# Pcbdesign_power_module.net
KiCad netlist of a schematic drawn in EAGLE
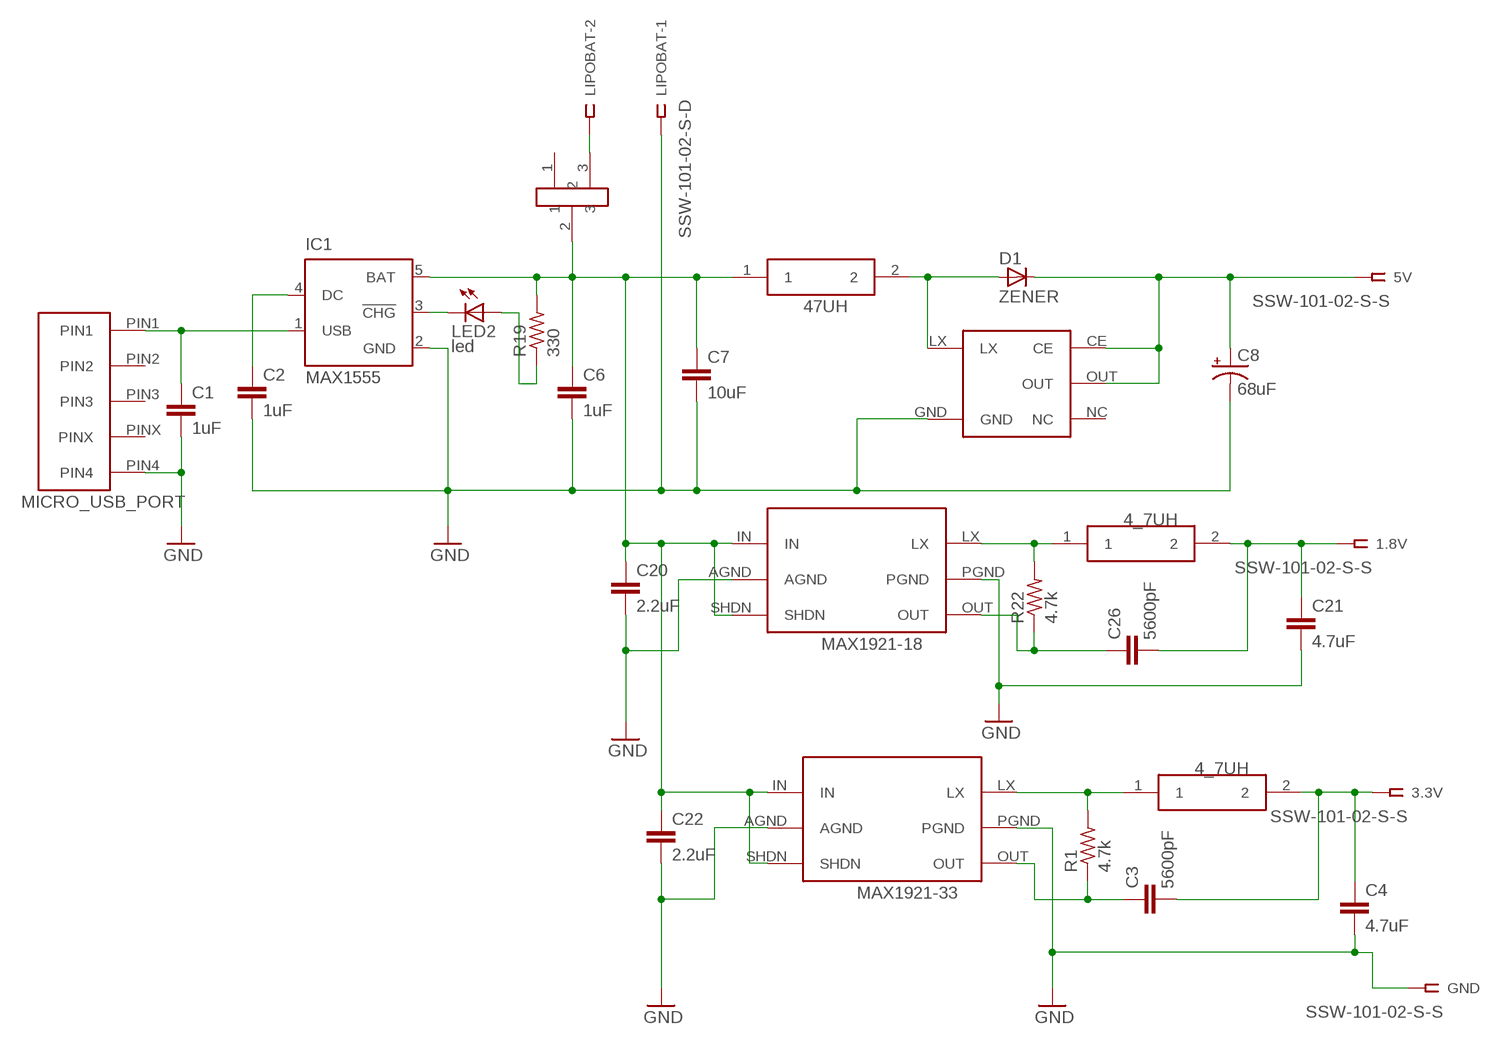
[diagram p0: schematic, sheet 1]

(export (version "E")
  (design (tool "Eeschema 10.0.6"))
  (components
    (comp (ref "1.8V")
      (value "SSW-101-02-S-S")
      (footprint "eagle-import:SSW-101-02-S-S")
      (libsource (lib "eagle-import") (part "SSW-101-02-S-S"))
    )
    (comp (ref "3.3V")
      (value "SSW-101-02-S-S")
      (footprint "eagle-import:SSW-101-02-S-S")
      (libsource (lib "eagle-import") (part "SSW-101-02-S-S"))
    )
    (comp (ref "5V")
      (value "SSW-101-02-S-S")
      (footprint "eagle-import:SSW-101-02-S-S")
      (libsource (lib "eagle-import") (part "SSW-101-02-S-S"))
    )
    (comp (ref "10UH")
      (value "SUMIDA_10U")
      (footprint "eagle-import:SUMIDA_10U")
      (libsource (lib "eagle-import") (part "SUMIDA_10U"))
    )
    (comp (ref "C1")
      (value "1uF")
      (footprint "eagle-import:C0805K")
      (libsource (lib "eagle-import") (part "C-EUC0805K"))
    )
    (comp (ref "C2")
      (value "1uF")
      (footprint "eagle-import:C0805K")
      (libsource (lib "eagle-import") (part "C-EUC0805K"))
    )
    (comp (ref "C3")
      (value "5600pF")
      (footprint "eagle-import:C0805K")
      (libsource (lib "eagle-import") (part "C-EUC0805K"))
    )
    (comp (ref "C4")
      (value "4.7uF")
      (footprint "eagle-import:C0805K")
      (libsource (lib "eagle-import") (part "C-EUC0805K"))
    )
    (comp (ref "C6")
      (value "1uF")
      (footprint "eagle-import:C0805K")
      (libsource (lib "eagle-import") (part "C-EUC0805K"))
    )
    (comp (ref "C7")
      (value "10uF")
      (footprint "eagle-import:C0805K")
      (libsource (lib "eagle-import") (part "C-EUC0805K"))
    )
    (comp (ref "C8")
      (value "68uF")
      (footprint "eagle-import:C_6032-28R")
      (libsource (lib "eagle-import") (part "CPOL-USC/6032-28R"))
    )
    (comp (ref "C20")
      (value "2.2uF")
      (footprint "eagle-import:C0805K")
      (libsource (lib "eagle-import") (part "C-EUC0805K"))
    )
    (comp (ref "C21")
      (value "4.7uF")
      (footprint "eagle-import:C0805K")
      (libsource (lib "eagle-import") (part "C-EUC0805K"))
    )
    (comp (ref "C22")
      (value "2.2uF")
      (footprint "eagle-import:C0805K")
      (libsource (lib "eagle-import") (part "C-EUC0805K"))
    )
    (comp (ref "C26")
      (value "5600pF")
      (footprint "eagle-import:C0805K")
      (libsource (lib "eagle-import") (part "C-EUC0805K"))
    )
    (comp (ref "D1")
      (value "ZENER")
      (footprint "eagle-import:SOD123")
      (libsource (lib "eagle-import") (part "D-SOD123"))
    )
    (comp (ref "GND")
      (value "SSW-101-02-S-S")
      (footprint "eagle-import:SSW-101-02-S-S")
      (libsource (lib "eagle-import") (part "SSW-101-02-S-S"))
    )
    (comp (ref "IC1")
      (value "MAX1555")
      (footprint "eagle-import:SOT23-5L")
      (fields (field (name "MF") "MAXIM") (field (name "MPN") "MAX1555EZK+T"))
      (libsource (lib "eagle-import") (part "MAX1555"))
    )
    (comp (ref "LED2")
      (value "led")
      (footprint "eagle-import:CHIPLED_0603")
      (libsource (lib "eagle-import") (part "LEDCHIPLED_0603"))
    )
    (comp (ref "LIPOBAT")
      (value "SSW-101-02-S-D")
      (footprint "eagle-import:SSW-101-02-S-D")
      (libsource (lib "eagle-import") (part "SSW-101-02-S-D"))
    )
    (comp (ref "MAX1920")
      (value "MAX1921")
      (footprint "eagle-import:MAX1921")
      (libsource (lib "eagle-import") (part "MAX1921"))
    )
    (comp (ref "MAX1921-18")
      (value "MAX1921")
      (footprint "eagle-import:MAX1921")
      (libsource (lib "eagle-import") (part "MAX1921"))
    )
    (comp (ref "MICRO_USB")
      (value "10118192")
      (footprint "eagle-import:10118192")
      (libsource (lib "eagle-import") (part "10118192"))
    )
    (comp (ref "R1")
      (value "4.7k")
      (footprint "eagle-import:R0805")
      (libsource (lib "eagle-import") (part "R-US_R0805"))
    )
    (comp (ref "R19")
      (value "330")
      (footprint "eagle-import:R0805")
      (libsource (lib "eagle-import") (part "R-US_R0805"))
    )
    (comp (ref "R22")
      (value "4.7k")
      (footprint "eagle-import:R0805")
      (libsource (lib "eagle-import") (part "R-US_R0805"))
    )
    (comp (ref "U$1")
      (value "SUMIDA_4.7U")
      (footprint "eagle-import:SUMIDA_4.7U")
      (libsource (lib "eagle-import") (part "SUMIDA_4.7U"))
    )
    (comp (ref "U$2")
      (value "SUMIDA_4.7U")
      (footprint "eagle-import:SUMIDA_4.7U")
      (libsource (lib "eagle-import") (part "SUMIDA_4.7U"))
    )
    (comp (ref "U$3")
      (value "NPC1402")
      (footprint "eagle-import:NPC1402")
      (libsource (lib "eagle-import") (part "NPC1402"))
    )
    (comp (ref "U$4")
      (value "SWITCH111")
      (footprint "eagle-import:SWITCH111")
      (libsource (lib "eagle-import") (part "SWITCH111"))
    )
  )
  (nets
    (net (code "1") (name "GND") (class "Default")
      (node (ref "C1") (pin "2") (pinfunction "2_2") (pintype "passive"))
      (node (ref "C2") (pin "2") (pinfunction "2_2") (pintype "passive"))
      (node (ref "C20") (pin "2") (pinfunction "2_2") (pintype "passive"))
      (node (ref "C21") (pin "2") (pinfunction "2_2") (pintype "passive"))
      (node (ref "C22") (pin "2") (pinfunction "2_2") (pintype "passive"))
      (node (ref "C4") (pin "2") (pinfunction "2_2") (pintype "passive"))
      (node (ref "C6") (pin "2") (pinfunction "2_2") (pintype "passive"))
      (node (ref "C7") (pin "2") (pinfunction "2_2") (pintype "passive"))
      (node (ref "C8") (pin "-") (pinfunction "-_-") (pintype "passive"))
      (node (ref "GND") (pin "1") (pinfunction "1_1") (pintype "passive"))
      (node (ref "IC1") (pin "2") (pinfunction "GND_2") (pintype "power_in"))
      (node (ref "LIPOBAT") (pin "1") (pinfunction "1_1") (pintype "passive"))
      (node (ref "MAX1920") (pin "AGND") (pinfunction "AGND_AGND") (pintype "bidirectional"))
      (node (ref "MAX1920") (pin "PGND") (pinfunction "PGND_PGND") (pintype "bidirectional"))
      (node (ref "MAX1921-18") (pin "AGND") (pinfunction "AGND_AGND") (pintype "bidirectional"))
      (node (ref "MAX1921-18") (pin "PGND") (pinfunction "PGND_PGND") (pintype "bidirectional"))
      (node (ref "MICRO_USB") (pin "PIN4") (pinfunction "PIN4_PIN4") (pintype "bidirectional"))
      (node (ref "U$3") (pin "GND") (pinfunction "GND_GND") (pintype "bidirectional"))
    )
    (net (code "2") (name "Net-(1.8V-Pad1)") (class "Default")
      (node (ref "1.8V") (pin "1") (pinfunction "1_1") (pintype "passive"))
      (node (ref "C21") (pin "1") (pinfunction "1_1") (pintype "passive"))
      (node (ref "C26") (pin "2") (pinfunction "2_2") (pintype "passive"))
      (node (ref "U$1") (pin "2") (pinfunction "2_2") (pintype "bidirectional"))
    )
    (net (code "3") (name "Net-(3.3V-Pad1)") (class "Default")
      (node (ref "3.3V") (pin "1") (pinfunction "1_1") (pintype "passive"))
      (node (ref "C3") (pin "2") (pinfunction "2_2") (pintype "passive"))
      (node (ref "C4") (pin "1") (pinfunction "1_1") (pintype "passive"))
      (node (ref "U$2") (pin "2") (pinfunction "2_2") (pintype "bidirectional"))
    )
    (net (code "4") (name "Net-(C3-Pad1)") (class "Default")
      (node (ref "C3") (pin "1") (pinfunction "1_1") (pintype "passive"))
      (node (ref "MAX1920") (pin "OUT") (pinfunction "OUT_OUT") (pintype "bidirectional"))
      (node (ref "R1") (pin "1") (pinfunction "1_1") (pintype "passive"))
    )
    (net (code "5") (name "Net-(C26-Pad1)") (class "Default")
      (node (ref "C26") (pin "1") (pinfunction "1_1") (pintype "passive"))
      (node (ref "MAX1921-18") (pin "OUT") (pinfunction "OUT_OUT") (pintype "bidirectional"))
      (node (ref "R22") (pin "1") (pinfunction "1_1") (pintype "passive"))
    )
    (net (code "6") (name "Net-(D1-A)") (class "Default")
      (node (ref "10UH") (pin "2") (pinfunction "2_2") (pintype "bidirectional"))
      (node (ref "D1") (pin "2") (pinfunction "A_2") (pintype "passive"))
      (node (ref "U$3") (pin "LX") (pinfunction "LX_LX") (pintype "bidirectional"))
    )
    (net (code "7") (name "Net-(D1-C)") (class "Default")
      (node (ref "5V") (pin "1") (pinfunction "1_1") (pintype "passive"))
      (node (ref "C8") (pin "+") (pinfunction "+_+") (pintype "passive"))
      (node (ref "D1") (pin "1") (pinfunction "C_1") (pintype "passive"))
      (node (ref "U$3") (pin "CE") (pinfunction "CE_CE") (pintype "bidirectional"))
      (node (ref "U$3") (pin "OUT") (pinfunction "OUT_OUT") (pintype "bidirectional"))
    )
    (net (code "8") (name "Net-(IC1-BAT)") (class "Default")
      (node (ref "10UH") (pin "1") (pinfunction "1_1") (pintype "bidirectional"))
      (node (ref "C20") (pin "1") (pinfunction "1_1") (pintype "passive"))
      (node (ref "C22") (pin "1") (pinfunction "1_1") (pintype "passive"))
      (node (ref "C6") (pin "1") (pinfunction "1_1") (pintype "passive"))
      (node (ref "C7") (pin "1") (pinfunction "1_1") (pintype "passive"))
      (node (ref "IC1") (pin "5") (pinfunction "BAT_5") (pintype "passive"))
      (node (ref "MAX1920") (pin "IN") (pinfunction "IN_IN") (pintype "bidirectional"))
      (node (ref "MAX1920") (pin "SHDN") (pinfunction "SHDN_SHDN") (pintype "bidirectional"))
      (node (ref "MAX1921-18") (pin "IN") (pinfunction "IN_IN") (pintype "bidirectional"))
      (node (ref "MAX1921-18") (pin "SHDN") (pinfunction "SHDN_SHDN") (pintype "bidirectional"))
      (node (ref "R19") (pin "2") (pinfunction "2_2") (pintype "passive"))
      (node (ref "U$4") (pin "2") (pinfunction "2_2") (pintype "bidirectional"))
    )
    (net (code "9") (name "Net-(IC1-DC)") (class "Default")
      (node (ref "C2") (pin "1") (pinfunction "1_1") (pintype "passive"))
      (node (ref "IC1") (pin "4") (pinfunction "DC_4") (pintype "input"))
    )
    (net (code "10") (name "Net-(IC1-USB)") (class "Default")
      (node (ref "C1") (pin "1") (pinfunction "1_1") (pintype "passive"))
      (node (ref "IC1") (pin "1") (pinfunction "USB_1") (pintype "input"))
      (node (ref "MICRO_USB") (pin "PIN1") (pinfunction "PIN1_PIN1") (pintype "bidirectional"))
    )
    (net (code "11") (name "Net-(IC1-~{CHG})") (class "Default")
      (node (ref "IC1") (pin "3") (pinfunction "~{CHG}_3") (pintype "output"))
      (node (ref "LED2") (pin "C") (pinfunction "C_C") (pintype "passive"))
    )
    (net (code "12") (name "Net-(LED2-PadA)") (class "Default")
      (node (ref "LED2") (pin "A") (pinfunction "A_A") (pintype "passive"))
      (node (ref "R19") (pin "1") (pinfunction "1_1") (pintype "passive"))
    )
    (net (code "13") (name "Net-(LIPOBATB-1)") (class "Default")
      (node (ref "LIPOBAT") (pin "2") (pinfunction "1_2") (pintype "passive"))
      (node (ref "U$4") (pin "3") (pinfunction "3_3") (pintype "bidirectional"))
    )
    (net (code "14") (name "Net-(MAX1920-PadLX)") (class "Default")
      (node (ref "MAX1920") (pin "LX") (pinfunction "LX_LX") (pintype "bidirectional"))
      (node (ref "R1") (pin "2") (pinfunction "2_2") (pintype "passive"))
      (node (ref "U$2") (pin "1") (pinfunction "1_1") (pintype "bidirectional"))
    )
    (net (code "15") (name "Net-(MAX1921-18-PadLX)") (class "Default")
      (node (ref "MAX1921-18") (pin "LX") (pinfunction "LX_LX") (pintype "bidirectional"))
      (node (ref "R22") (pin "2") (pinfunction "2_2") (pintype "passive"))
      (node (ref "U$1") (pin "1") (pinfunction "1_1") (pintype "bidirectional"))
    )
    (net (code "16") (name "unconnected-(MICRO_USB-PadPIN2)") (class "Default")
      (node (ref "MICRO_USB") (pin "PIN2") (pinfunction "PIN2_PIN2") (pintype "bidirectional"))
    )
    (net (code "17") (name "unconnected-(MICRO_USB-PadPIN3)") (class "Default")
      (node (ref "MICRO_USB") (pin "PIN3") (pinfunction "PIN3_PIN3") (pintype "bidirectional"))
    )
    (net (code "18") (name "unconnected-(MICRO_USB-PadPINX)") (class "Default")
      (node (ref "MICRO_USB") (pin "PINX") (pinfunction "PINX_PINX") (pintype "bidirectional"))
    )
    (net (code "19") (name "unconnected-(U$3-PadNC)") (class "Default")
      (node (ref "U$3") (pin "NC") (pinfunction "NC_NC") (pintype "bidirectional"))
    )
    (net (code "20") (name "unconnected-(U$4-Pad1)") (class "Default")
      (node (ref "U$4") (pin "1") (pinfunction "1_1") (pintype "bidirectional"))
    )
  )
)
